# MCU.net
KiCad netlist of a schematic drawn in Altium Designer
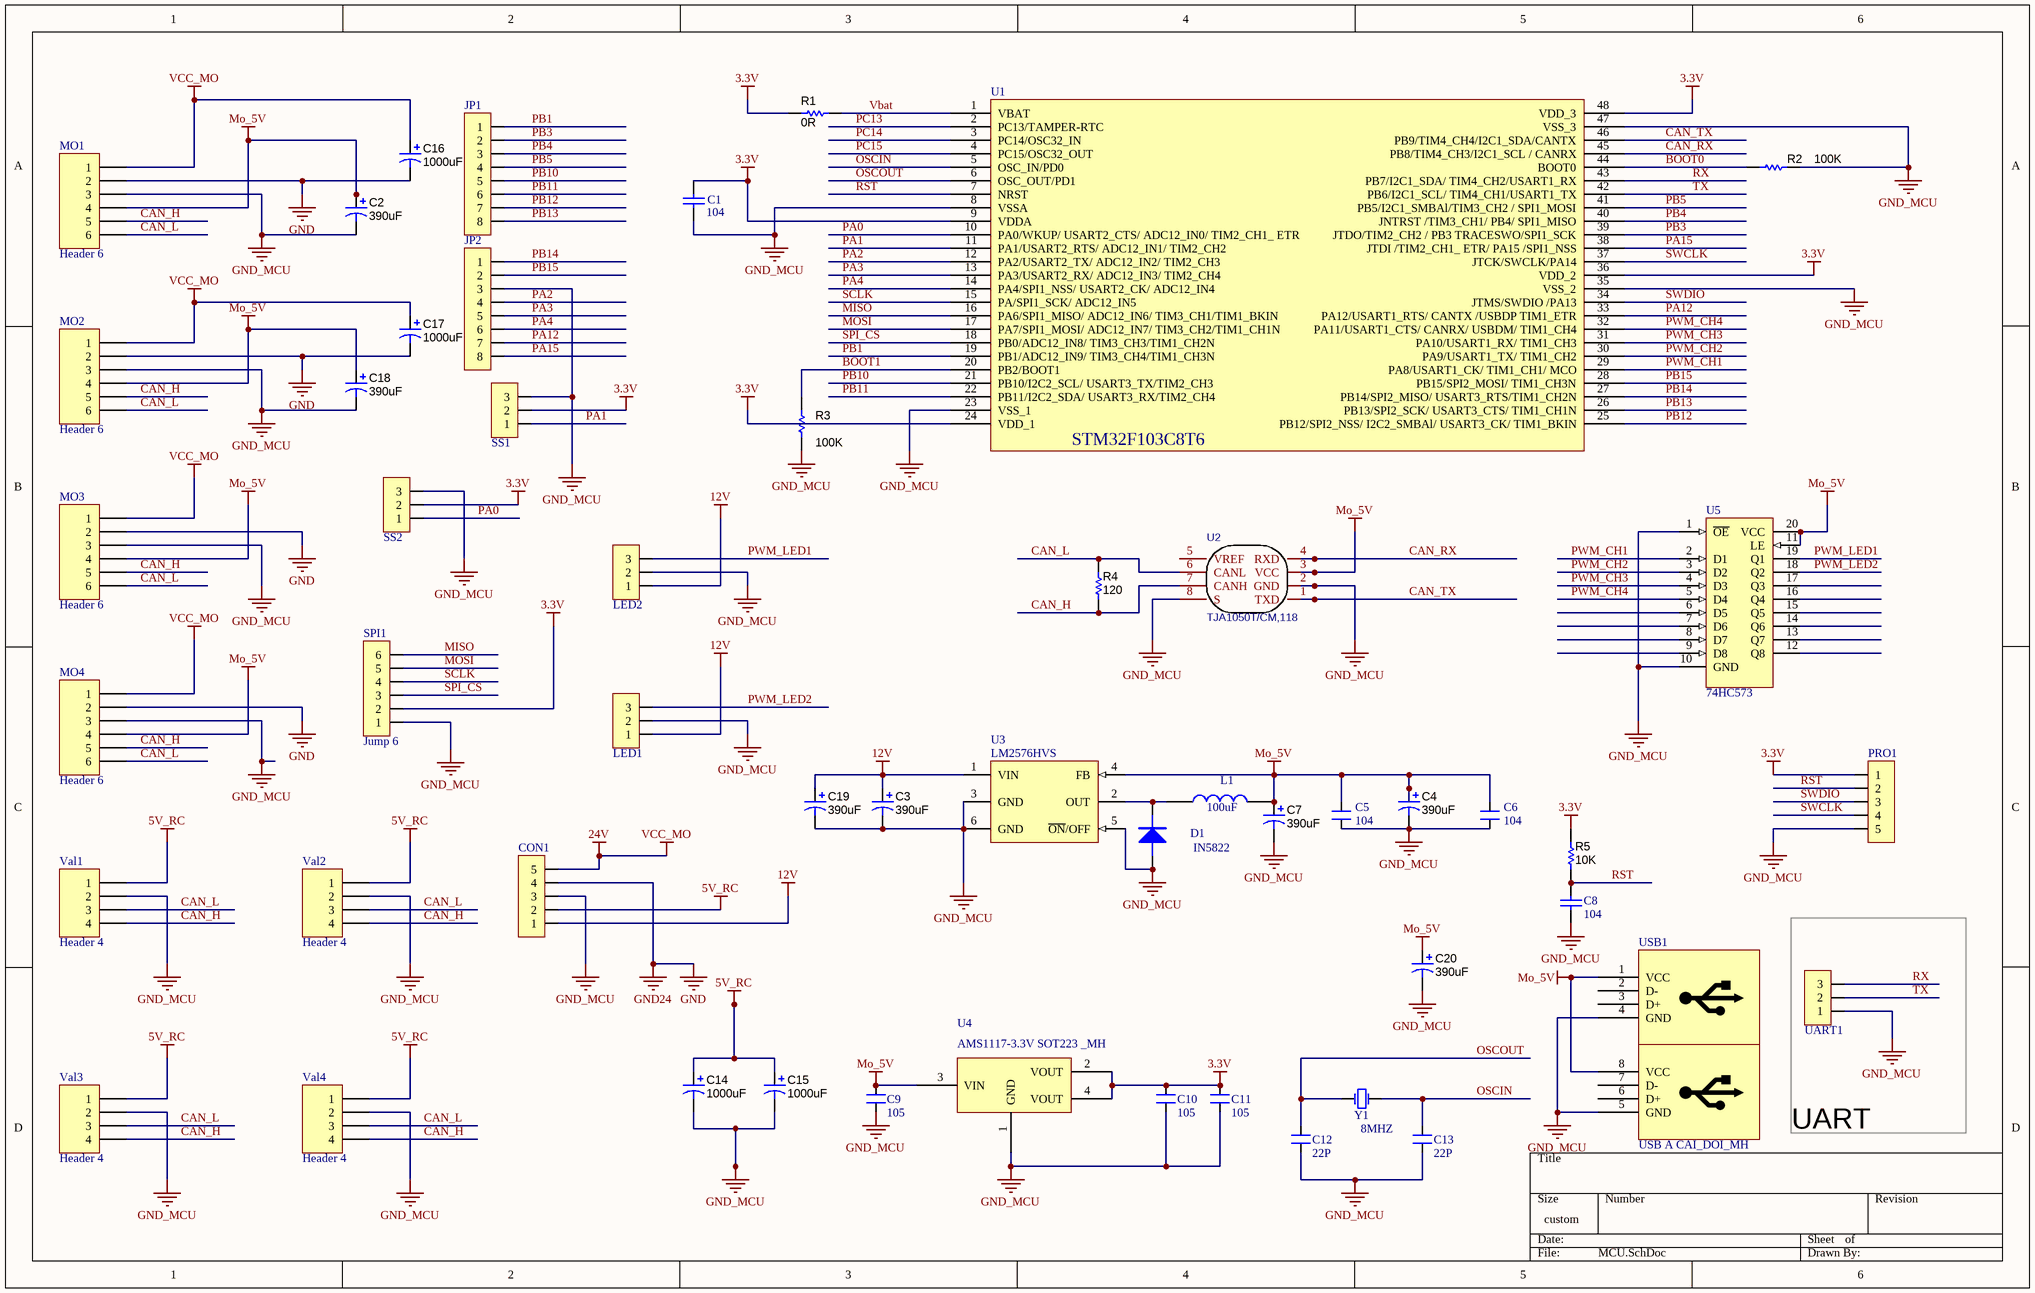
[diagram p0: MCU.SchDoc]

(export (version "E")
  (design (tool "Eeschema 10.0.6"))
  (components
    (comp (ref "C1")
      (value "104")
      (footprint "0805_HV")
      (description "Ceramic Chip Capacitor - Standard")
      (fields (field (name "PUBLISHER") "Altium Limited"))
      (libsource (lib "mySch") (part "Capacitor 0805"))
    )
    (comp (ref "C2")
      (value "390uF")
      (footprint "CP1/3.0")
      (fields
        (field (name "PARTNUMBER") "UHW1H391MPD6")
        (field (name "MANUFACTURER") "Nichicon")
        (field (name "VALUEDISPLAYED") "390uF")
        (field (name "PUBLISHER") "Texas Instruments")
      )
      (libsource (lib "mySch") (part "Capacitor TuHoa"))
    )
    (comp (ref "C3")
      (value "390uF")
      (footprint "CP1/3.0")
      (fields
        (field (name "PARTNUMBER") "UHW1H391MPD6")
        (field (name "MANUFACTURER") "Nichicon")
        (field (name "VALUEDISPLAYED") "390uF")
        (field (name "PUBLISHER") "Texas Instruments")
      )
      (libsource (lib "mySch") (part "Capacitor TuHoa"))
    )
    (comp (ref "C4")
      (value "390uF")
      (footprint "CP1/3.0")
      (fields
        (field (name "PARTNUMBER") "UHW1H391MPD6")
        (field (name "MANUFACTURER") "Nichicon")
        (field (name "VALUEDISPLAYED") "390uF")
        (field (name "PUBLISHER") "Texas Instruments")
      )
      (libsource (lib "mySch") (part "Capacitor TuHoa"))
    )
    (comp (ref "C5")
      (value "104")
      (footprint "0805_HV")
      (description "Cap SMD")
      (libsource (lib "hatcatbietbay") (part "CM"))
    )
    (comp (ref "C6")
      (value "104")
      (footprint "0805_HV")
      (description "Cap SMD")
      (libsource (lib "hatcatbietbay") (part "CM"))
    )
    (comp (ref "C7")
      (value "390uF")
      (footprint "CP1/3.0")
      (fields
        (field (name "PARTNUMBER") "UHW1H391MPD6")
        (field (name "MANUFACTURER") "Nichicon")
        (field (name "VALUEDISPLAYED") "390uF")
        (field (name "PUBLISHER") "Texas Instruments")
      )
      (libsource (lib "mySch") (part "Capacitor TuHoa"))
    )
    (comp (ref "C8")
      (value "104")
      (footprint "0805_HV")
      (description "Ceramic Chip Capacitor - Standard")
      (fields (field (name "PUBLISHER") "Altium Limited"))
      (libsource (lib "mySch") (part "Capacitor 0805"))
    )
    (comp (ref "C9")
      (value "105")
      (footprint "0805_HV")
      (description "Cap SMD")
      (libsource (lib "hatcatbietbay") (part "CM"))
    )
    (comp (ref "C10")
      (value "105")
      (footprint "0805_HV")
      (description "Cap SMD")
      (libsource (lib "hatcatbietbay") (part "CM"))
    )
    (comp (ref "C11")
      (value "105")
      (footprint "0805_HV")
      (description "Cap SMD")
      (libsource (lib "hatcatbietbay") (part "CM"))
    )
    (comp (ref "C12")
      (value "22P")
      (footprint "0805_HV")
      (description "Cap SMD")
      (libsource (lib "hatcatbietbay") (part "CM"))
    )
    (comp (ref "C13")
      (value "22P")
      (footprint "0805_HV")
      (description "Cap SMD")
      (libsource (lib "hatcatbietbay") (part "CM"))
    )
    (comp (ref "C14")
      (value "390uF")
      (footprint "CAP_12.5 X 25")
      (description "CAP ALUM 390UF 20% 50V RADIAL")
      (fields
        (field (name "PARTNUMBER") "UHW1H391MPD6")
        (field (name "MANUFACTURER") "Nichicon")
        (field (name "VALUEDISPLAYED") "1000uF")
        (field (name "PUBLISHER") "Texas Instruments")
      )
      (libsource (lib "mySch") (part "Capacitor TuHoa"))
    )
    (comp (ref "C15")
      (value "390uF")
      (footprint "CAP_12.5 X 25")
      (description "CAP ALUM 390UF 20% 50V RADIAL")
      (fields
        (field (name "PARTNUMBER") "UHW1H391MPD6")
        (field (name "MANUFACTURER") "Nichicon")
        (field (name "VALUEDISPLAYED") "1000uF")
        (field (name "PUBLISHER") "Texas Instruments")
      )
      (libsource (lib "mySch") (part "Capacitor TuHoa"))
    )
    (comp (ref "C16")
      (value "390uF")
      (footprint "CAP_12.5 X 25")
      (description "CAP ALUM 390UF 20% 50V RADIAL")
      (fields
        (field (name "PARTNUMBER") "UHW1H391MPD6")
        (field (name "MANUFACTURER") "Nichicon")
        (field (name "VALUEDISPLAYED") "1000uF")
        (field (name "PUBLISHER") "Texas Instruments")
      )
      (libsource (lib "mySch") (part "Capacitor TuHoa"))
    )
    (comp (ref "C17")
      (value "390uF")
      (footprint "CAP_12.5 X 25")
      (description "CAP ALUM 390UF 20% 50V RADIAL")
      (fields
        (field (name "PARTNUMBER") "UHW1H391MPD6")
        (field (name "MANUFACTURER") "Nichicon")
        (field (name "VALUEDISPLAYED") "1000uF")
        (field (name "PUBLISHER") "Texas Instruments")
      )
      (libsource (lib "mySch") (part "Capacitor TuHoa"))
    )
    (comp (ref "C18")
      (value "390uF")
      (footprint "CP1/3.0")
      (fields
        (field (name "PARTNUMBER") "UHW1H391MPD6")
        (field (name "MANUFACTURER") "Nichicon")
        (field (name "VALUEDISPLAYED") "390uF")
        (field (name "PUBLISHER") "Texas Instruments")
      )
      (libsource (lib "mySch") (part "Capacitor TuHoa"))
    )
    (comp (ref "C19")
      (value "390uF")
      (footprint "CP1/3.0")
      (fields
        (field (name "PARTNUMBER") "UHW1H391MPD6")
        (field (name "MANUFACTURER") "Nichicon")
        (field (name "VALUEDISPLAYED") "390uF")
        (field (name "PUBLISHER") "Texas Instruments")
      )
      (libsource (lib "mySch") (part "Capacitor TuHoa"))
    )
    (comp (ref "C20")
      (value "390uF")
      (footprint "CP1/3.0")
      (fields
        (field (name "PARTNUMBER") "UHW1H391MPD6")
        (field (name "MANUFACTURER") "Nichicon")
        (field (name "VALUEDISPLAYED") "390uF")
        (field (name "PUBLISHER") "Texas Instruments")
      )
      (libsource (lib "mySch") (part "Capacitor TuHoa"))
    )
    (comp (ref "CON1")
      (value "CON 5 EDG 5.08_MH")
      (footprint "Con 5 EDG 5.08")
      (description "CON 5 EDG 5.08 (xanh cong)")
      (libsource (lib "MH_DA_THU_VIEN_16122016") (part "CON 5 EDG 5.08_MH"))
    )
    (comp (ref "D1")
      (value "IN5822")
      (footprint "SOD123")
      (description "Diode S4 SOD123 ( 1N5819 SOD123)")
      (libsource (lib "MH_DA_THU_VIEN_16122016") (part "Diode S4 SOD123 ( 1N5819 SOD123)_MH"))
    )
    (comp (ref "JP1")
      (value "Jump 8_MH")
      (footprint "Jump 8")
      (description "Jump 8P 2.54")
      (libsource (lib "MH_DA_THU_VIEN_16122016") (part "Jump 8_MH"))
    )
    (comp (ref "JP2")
      (value "Jump 8_MH")
      (footprint "Jump 8")
      (description "Jump 8P 2.54")
      (libsource (lib "MH_DA_THU_VIEN_16122016") (part "Jump 8_MH"))
    )
    (comp (ref "L1")
      (value "100uF")
      (footprint "IND_2118-V-RC")
      (description "cuon cam")
      (libsource (lib "MH_DA_THU_VIEN_16122016") (part "Inductor Lm2576_MH"))
    )
    (comp (ref "LED1")
      (value "Header 3_MH")
      (footprint "HEADER 3")
      (description "Header 3P XH2.54 thẳng")
      (libsource (lib "MH_DA_THU_VIEN_16122016") (part "Header 3_MH"))
    )
    (comp (ref "LED2")
      (value "Header 3_MH")
      (footprint "HEADER 3")
      (description "Header 3P XH2.54 thẳng")
      (libsource (lib "MH_DA_THU_VIEN_16122016") (part "Header 3_MH"))
    )
    (comp (ref "MO1")
      (value "Header 6")
      (footprint "HEADER 6")
      (description "Header, 6-Pin")
      (fields (field (name "PUBLISHER") "Altium Limited"))
      (libsource (lib "MH_DA_THU_VIEN_16122016") (part "Header 6"))
    )
    (comp (ref "MO2")
      (value "Header 6")
      (footprint "HEADER 6")
      (description "Header, 6-Pin")
      (fields (field (name "PUBLISHER") "Altium Limited"))
      (libsource (lib "MH_DA_THU_VIEN_16122016") (part "Header 6"))
    )
    (comp (ref "MO3")
      (value "Header 6")
      (footprint "HEADER 6")
      (description "Header, 6-Pin")
      (fields (field (name "PUBLISHER") "Altium Limited"))
      (libsource (lib "MH_DA_THU_VIEN_16122016") (part "Header 6"))
    )
    (comp (ref "MO4")
      (value "Header 6")
      (footprint "HEADER 6")
      (description "Header, 6-Pin")
      (fields (field (name "PUBLISHER") "Altium Limited"))
      (libsource (lib "MH_DA_THU_VIEN_16122016") (part "Header 6"))
    )
    (comp (ref "PRO1")
      (value "Header 5_MH")
      (footprint "HEADER 5")
      (description "Header 5P XH2.54 thẳng")
      (libsource (lib "MH_DA_THU_VIEN_16122016") (part "Header 5_MH"))
    )
    (comp (ref "R1")
      (value "0R")
      (footprint "0805_HV")
      (description "RES, 100, 1%, 0.1 W, 0402")
      (fields
        (field (name "PARTNUMBER") "ERJ-2RKF1000X")
        (field (name "MANUFACTURER") "Panasonic")
        (field (name "PUBLISHER") "Texas Instruments")
      )
      (libsource (lib "mySch") (part "R nho"))
    )
    (comp (ref "R2")
      (value "100K")
      (footprint "0805_HV")
      (description "RES, 100, 1%, 0.1 W, 0402")
      (fields
        (field (name "PARTNUMBER") "ERJ-2RKF1000X")
        (field (name "MANUFACTURER") "Panasonic")
        (field (name "PUBLISHER") "Texas Instruments")
      )
      (libsource (lib "mySch") (part "R nho"))
    )
    (comp (ref "R3")
      (value "100K")
      (footprint "0805_HV")
      (description "RES, 100, 1%, 0.1 W, 0402")
      (fields
        (field (name "PARTNUMBER") "ERJ-2RKF1000X")
        (field (name "MANUFACTURER") "Panasonic")
        (field (name "PUBLISHER") "Texas Instruments")
      )
      (libsource (lib "mySch") (part "R nho"))
    )
    (comp (ref "R4")
      (value "120")
      (footprint "0805_HV")
      (description "RES, 100, 1%, 0.1 W, 0402")
      (fields
        (field (name "PARTNUMBER") "ERJ-2RKF1000X")
        (field (name "MANUFACTURER") "Panasonic")
        (field (name "PUBLISHER") "Texas Instruments")
      )
      (libsource (lib "mySch") (part "R nho"))
    )
    (comp (ref "R5")
      (value "10K")
      (footprint "0805_HV")
      (description "RES, 100, 1%, 0.1 W, 0402")
      (fields
        (field (name "PARTNUMBER") "ERJ-2RKF1000X")
        (field (name "MANUFACTURER") "Panasonic")
        (field (name "PUBLISHER") "Texas Instruments")
      )
      (libsource (lib "mySch") (part "R nho"))
    )
    (comp (ref "SPI1")
      (value "Jump 6")
      (footprint "ZH 1.5 6P")
      (description "Jump 6P 2.54")
      (libsource (lib "mySch") (part "Jump 6"))
    )
    (comp (ref "SS1")
      (value "Header 3_MH")
      (footprint "HEADER 3")
      (description "Header 3P XH2.54 thẳng")
      (libsource (lib "MH_DA_THU_VIEN_16122016") (part "Header 3_MH"))
    )
    (comp (ref "SS2")
      (value "Header 3_MH")
      (footprint "HEADER 3")
      (description "Header 3P XH2.54 thẳng")
      (libsource (lib "MH_DA_THU_VIEN_16122016") (part "Header 3_MH"))
    )
    (comp (ref "U1")
      (value "STM32F103C8T6 LQFP48 _MH")
      (footprint "LQFP48")
      (libsource (lib "MH_DA_THU_VIEN_16122016") (part "STM32F103C8T6 LQFP48 _MH"))
    )
    (comp (ref "U2")
      (value "TJA1050T/CM,118")
      (footprint "SOP 8")
      (fields (field (name "BOM_SUPPLIER PART") "C6952"))
      (libsource (lib "Schlib1") (part "TJA1050T/CM,118"))
    )
    (comp (ref "U3")
      (value "LM2576HVS")
      (footprint "TO263-5")
      (description "LM2576HVS-5.0V BUCK 5V 3A TO263-5 _MH")
      (fields
        (field (name "PARTNUMBER") "LM2576T-5.0")
        (field (name "MANUFACTURER") "National Semiconductor")
        (field (name "PUBLISHER") "Altium Limited")
      )
      (libsource (lib "MH_DA_THU_VIEN_16122016") (part "LM2576HVS-5.0V BUCK 5V 3A TO263-5 _MH"))
    )
    (comp (ref "U4")
      (value "AMS1117-3.3V SOT223 _MH")
      (footprint "SOT223")
      (libsource (lib "MH_DA_THU_VIEN_16122016") (part "AMS1117-3.3V SOT223 _MH"))
    )
    (comp (ref "U5")
      (value "74HC573")
      (footprint "SOIC-20")
      (description "Octal D-Type Latch with 3-State Output Non-Inverting")
      (fields (field (name "COPYRIGHT BY") "VanDungEvn@Gmail.com"))
      (libsource (lib "MH_DA_THU_VIEN_16122016") (part "74HC573 DIP20 IC Flip-Flop_MH"))
    )
    (comp (ref "UART1")
      (value "Header 3_MH")
      (footprint "HEADER 3")
      (description "Header 3P XH2.54 thẳng")
      (libsource (lib "MH_DA_THU_VIEN_16122016") (part "Header 3_MH"))
    )
    (comp (ref "USB1")
      (value "USB A CAI_DOI_MH")
      (footprint "USB_KEP")
      (libsource (lib "MH_DA_THU_VIEN_16122016") (part "USB A CAI_DOI_MH"))
    )
    (comp (ref "Val1")
      (value "Header 4")
      (footprint "JST-PH2.00-4P")
      (description "Header, 4-Pin")
      (fields (field (name "PUBLISHER") "Altium Limited"))
      (libsource (lib "Miscellaneous Connectors") (part "Header 4"))
    )
    (comp (ref "Val2")
      (value "Header 4")
      (footprint "JST-PH2.00-4P")
      (description "Header, 4-Pin")
      (fields (field (name "PUBLISHER") "Altium Limited"))
      (libsource (lib "Miscellaneous Connectors") (part "Header 4"))
    )
    (comp (ref "Val3")
      (value "Header 4")
      (footprint "JST-PH2.00-4P")
      (description "Header, 4-Pin")
      (fields (field (name "PUBLISHER") "Altium Limited"))
      (libsource (lib "Miscellaneous Connectors") (part "Header 4"))
    )
    (comp (ref "Val4")
      (value "Header 4")
      (footprint "JST-PH2.00-4P")
      (description "Header, 4-Pin")
      (fields (field (name "PUBLISHER") "Altium Limited"))
      (libsource (lib "Miscellaneous Connectors") (part "Header 4"))
    )
    (comp (ref "Y1")
      (value "8MHZ")
      (footprint "XT2")
      (description "Crystal Oscillator")
      (fields (field (name "PUBLISHER") "Altium Limited"))
      (libsource (lib "MH_DA_THU_VIEN_16122016") (part "CRYSTAL_49S DIP_MH"))
    )
  )
  (nets
    (net (code "1") (name "/BOOT0") (class "Default")
      (node (ref "R2") (pin "2") (pinfunction "2_2") (pintype "passive"))
      (node (ref "U1") (pin "44") (pinfunction "BOOT0_44") (pintype "passive"))
    )
    (net (code "2") (name "/BOOT1") (class "Default")
      (node (ref "R3") (pin "1") (pinfunction "1_1") (pintype "passive"))
      (node (ref "U1") (pin "20") (pinfunction "PB2/BOOT1_20") (pintype "passive"))
    )
    (net (code "3") (name "/CAN_H") (class "Default")
      (node (ref "MO1") (pin "5") (pinfunction "5_5") (pintype "passive"))
      (node (ref "MO2") (pin "5") (pinfunction "5_5") (pintype "passive"))
      (node (ref "MO3") (pin "5") (pinfunction "5_5") (pintype "passive"))
      (node (ref "MO4") (pin "5") (pinfunction "5_5") (pintype "passive"))
      (node (ref "R4") (pin "2") (pinfunction "2_2") (pintype "passive"))
      (node (ref "U2") (pin "7") (pinfunction "CANH_7") (pintype "passive"))
      (node (ref "Val1") (pin "4") (pinfunction "4_4") (pintype "passive"))
      (node (ref "Val2") (pin "4") (pinfunction "4_4") (pintype "passive"))
      (node (ref "Val3") (pin "4") (pinfunction "4_4") (pintype "passive"))
      (node (ref "Val4") (pin "4") (pinfunction "4_4") (pintype "passive"))
    )
    (net (code "4") (name "/CAN_L") (class "Default")
      (node (ref "MO1") (pin "6") (pinfunction "6_6") (pintype "passive"))
      (node (ref "MO2") (pin "6") (pinfunction "6_6") (pintype "passive"))
      (node (ref "MO3") (pin "6") (pinfunction "6_6") (pintype "passive"))
      (node (ref "MO4") (pin "6") (pinfunction "6_6") (pintype "passive"))
      (node (ref "R4") (pin "1") (pinfunction "1_1") (pintype "passive"))
      (node (ref "U2") (pin "6") (pinfunction "CANL_6") (pintype "passive"))
      (node (ref "Val1") (pin "3") (pinfunction "3_3") (pintype "passive"))
      (node (ref "Val2") (pin "3") (pinfunction "3_3") (pintype "passive"))
      (node (ref "Val3") (pin "3") (pinfunction "3_3") (pintype "passive"))
      (node (ref "Val4") (pin "3") (pinfunction "3_3") (pintype "passive"))
    )
    (net (code "5") (name "/CAN_RX") (class "Default")
      (node (ref "U1") (pin "45") (pinfunction "PB8/TIM4_CH3/I2C1_SCL_/_CANRX_45") (pintype "passive"))
      (node (ref "U2") (pin "4") (pinfunction "RXD_4") (pintype "passive"))
    )
    (net (code "6") (name "/CAN_TX") (class "Default")
      (node (ref "U1") (pin "46") (pinfunction "PB9/TIM4_CH4/I2C1_SDA/CANTX_46") (pintype "passive"))
      (node (ref "U2") (pin "1") (pinfunction "TXD_1") (pintype "passive"))
    )
    (net (code "7") (name "/MISO") (class "Default")
      (node (ref "SPI1") (pin "6") (pinfunction "6_6") (pintype "passive"))
      (node (ref "U1") (pin "16") (pinfunction "PA6/SPI1_MISO/_ADC12_IN6/_TIM3_CH1/TIM1_BKIN_16") (pintype "passive"))
    )
    (net (code "8") (name "/MOSI") (class "Default")
      (node (ref "SPI1") (pin "5") (pinfunction "5_5") (pintype "passive"))
      (node (ref "U1") (pin "17") (pinfunction "PA7/SPI1_MOSI/_ADC12_IN7/_TIM3_CH2/TIM1_CH1N_17") (pintype "passive"))
    )
    (net (code "9") (name "/OSCIN") (class "Default")
      (node (ref "C13") (pin "2") (pinfunction "2_2") (pintype "passive"))
      (node (ref "U1") (pin "5") (pinfunction "OSC_IN/PD0_5") (pintype "passive"))
      (node (ref "Y1") (pin "2") (pinfunction "OSC2_2") (pintype "passive"))
    )
    (net (code "10") (name "/OSCOUT") (class "Default")
      (node (ref "C12") (pin "2") (pinfunction "2_2") (pintype "passive"))
      (node (ref "U1") (pin "6") (pinfunction "OSC_OUT/PD1_6") (pintype "passive"))
      (node (ref "Y1") (pin "1") (pinfunction "OSC1_1") (pintype "passive"))
    )
    (net (code "11") (name "/PA0") (class "Default")
      (node (ref "SS2") (pin "1") (pinfunction "1_1") (pintype "passive"))
      (node (ref "U1") (pin "10") (pinfunction "PA0/WKUP/_USART2_CTS/_ADC12_IN0/_TIM2_CH1__ETR_10") (pintype "passive"))
    )
    (net (code "12") (name "/PA1") (class "Default")
      (node (ref "SS1") (pin "1") (pinfunction "1_1") (pintype "passive"))
      (node (ref "U1") (pin "11") (pinfunction "PA1/USART2_RTS/_ADC12_IN1/_TIM2_CH2_11") (pintype "passive"))
    )
    (net (code "13") (name "/PA2") (class "Default")
      (node (ref "JP2") (pin "4") (pinfunction "4_4") (pintype "passive"))
      (node (ref "U1") (pin "12") (pinfunction "PA2/USART2_TX/_ADC12_IN2/_TIM2_CH3_12") (pintype "passive"))
    )
    (net (code "14") (name "/PA3") (class "Default")
      (node (ref "JP2") (pin "5") (pinfunction "5_5") (pintype "passive"))
      (node (ref "U1") (pin "13") (pinfunction "PA3/USART2_RX/_ADC12_IN3/_TIM2_CH4_13") (pintype "passive"))
    )
    (net (code "15") (name "/PA4") (class "Default")
      (node (ref "JP2") (pin "6") (pinfunction "6_6") (pintype "passive"))
      (node (ref "U1") (pin "14") (pinfunction "PA4/SPI1_NSS/_USART2_CK/_ADC12_IN4_14") (pintype "passive"))
    )
    (net (code "16") (name "/PA12") (class "Default")
      (node (ref "JP2") (pin "7") (pinfunction "7_7") (pintype "passive"))
      (node (ref "U1") (pin "33") (pinfunction "PA12/USART1_RTS/_CANTX_/USBDP_TIM1_ETR_33") (pintype "passive"))
    )
    (net (code "17") (name "/PA15") (class "Default")
      (node (ref "JP2") (pin "8") (pinfunction "8_8") (pintype "passive"))
      (node (ref "U1") (pin "38") (pinfunction "JTDI_/TIM2_CH1__ETR/_PA15_/SPI1_NSS_38") (pintype "passive"))
    )
    (net (code "18") (name "/PB1") (class "Default")
      (node (ref "JP1") (pin "1") (pinfunction "1_1") (pintype "passive"))
      (node (ref "U1") (pin "19") (pinfunction "PB1/ADC12_IN9/_TIM3_CH4/TIM1_CH3N_19") (pintype "passive"))
    )
    (net (code "19") (name "/PB3") (class "Default")
      (node (ref "JP1") (pin "2") (pinfunction "2_2") (pintype "passive"))
      (node (ref "U1") (pin "39") (pinfunction "JTDO/TIM2_CH2_/_PB3_TRACESWO/SPI1_SCK_39") (pintype "passive"))
    )
    (net (code "20") (name "/PB4") (class "Default")
      (node (ref "JP1") (pin "3") (pinfunction "3_3") (pintype "passive"))
      (node (ref "U1") (pin "40") (pinfunction "JNTRST_/TIM3_CH1/_PB4/_SPI1_MISO_40") (pintype "passive"))
    )
    (net (code "21") (name "/PB5") (class "Default")
      (node (ref "JP1") (pin "4") (pinfunction "4_4") (pintype "passive"))
      (node (ref "U1") (pin "41") (pinfunction "PB5/I2C1_SMBAl/TIM3_CH2_/_SPI1_MOSI_41") (pintype "passive"))
    )
    (net (code "22") (name "/PB10") (class "Default")
      (node (ref "JP1") (pin "5") (pinfunction "5_5") (pintype "passive"))
      (node (ref "U1") (pin "21") (pinfunction "PB10/I2C2_SCL/_USART3_TX/TIM2_CH3_21") (pintype "passive"))
    )
    (net (code "23") (name "/PB11") (class "Default")
      (node (ref "JP1") (pin "6") (pinfunction "6_6") (pintype "passive"))
      (node (ref "U1") (pin "22") (pinfunction "PB11/I2C2_SDA/_USART3_RX/TIM2_CH4_22") (pintype "passive"))
    )
    (net (code "24") (name "/PB12") (class "Default")
      (node (ref "JP1") (pin "7") (pinfunction "7_7") (pintype "passive"))
      (node (ref "U1") (pin "25") (pinfunction "PB12/SPI2_NSS/_I2C2_SMBAl/_USART3_CK/_TIM1_BKIN_25") (pintype "passive"))
    )
    (net (code "25") (name "/PB13") (class "Default")
      (node (ref "JP1") (pin "8") (pinfunction "8_8") (pintype "passive"))
      (node (ref "U1") (pin "26") (pinfunction "PB13/SPI2_SCK/_USART3_CTS/_TIM1_CH1N_26") (pintype "passive"))
    )
    (net (code "26") (name "/PB14") (class "Default")
      (node (ref "JP2") (pin "1") (pinfunction "1_1") (pintype "passive"))
      (node (ref "U1") (pin "27") (pinfunction "PB14/SPI2_MISO/_USART3_RTS/TIM1_CH2N_27") (pintype "passive"))
    )
    (net (code "27") (name "/PB15") (class "Default")
      (node (ref "JP2") (pin "2") (pinfunction "2_2") (pintype "passive"))
      (node (ref "U1") (pin "28") (pinfunction "PB15/SPI2_MOSI/_TIM1_CH3N_28") (pintype "passive"))
    )
    (net (code "28") (name "/PC13") (class "Default")
      (node (ref "U1") (pin "2") (pinfunction "PC13/TAMPER-RTC_2") (pintype "passive"))
    )
    (net (code "29") (name "/PC14") (class "Default")
      (node (ref "U1") (pin "3") (pinfunction "PC14/OSC32_IN_3") (pintype "passive"))
    )
    (net (code "30") (name "/PC15") (class "Default")
      (node (ref "U1") (pin "4") (pinfunction "PC15/OSC32_OUT_4") (pintype "passive"))
    )
    (net (code "31") (name "/PWM_CH1") (class "Default")
      (node (ref "U1") (pin "29") (pinfunction "PA8/USART1_CK/_TIM1_CH1/_MCO_29") (pintype "passive"))
      (node (ref "U5") (pin "2") (pinfunction "D1_2") (pintype "input"))
    )
    (net (code "32") (name "/PWM_CH2") (class "Default")
      (node (ref "U1") (pin "30") (pinfunction "PA9/USART1_TX/_TIM1_CH2_30") (pintype "passive"))
      (node (ref "U5") (pin "3") (pinfunction "D2_3") (pintype "input"))
    )
    (net (code "33") (name "/PWM_CH3") (class "Default")
      (node (ref "U1") (pin "31") (pinfunction "PA10/USART1_RX/_TIM1_CH3_31") (pintype "passive"))
      (node (ref "U5") (pin "4") (pinfunction "D3_4") (pintype "input"))
    )
    (net (code "34") (name "/PWM_CH4") (class "Default")
      (node (ref "U1") (pin "32") (pinfunction "PA11/USART1_CTS/_CANRX/_USBDM/_TIM1_CH4_32") (pintype "passive"))
      (node (ref "U5") (pin "5") (pinfunction "D4_5") (pintype "input"))
    )
    (net (code "35") (name "/PWM_LED1") (class "Default")
      (node (ref "LED2") (pin "3") (pinfunction "3_3") (pintype "passive"))
      (node (ref "U5") (pin "19") (pinfunction "Q1_19") (pintype "tri_state"))
    )
    (net (code "36") (name "/PWM_LED2") (class "Default")
      (node (ref "LED1") (pin "3") (pinfunction "3_3") (pintype "passive"))
      (node (ref "U5") (pin "18") (pinfunction "Q2_18") (pintype "tri_state"))
    )
    (net (code "37") (name "/RST") (class "Default")
      (node (ref "C8") (pin "2") (pinfunction "2_2") (pintype "passive"))
      (node (ref "PRO1") (pin "2") (pinfunction "2_2") (pintype "passive"))
      (node (ref "R5") (pin "1") (pinfunction "1_1") (pintype "passive"))
      (node (ref "U1") (pin "7") (pinfunction "NRST_7") (pintype "passive"))
    )
    (net (code "38") (name "/RX") (class "Default")
      (node (ref "U1") (pin "43") (pinfunction "PB7/I2C1_SDA/_TIM4_CH2/USART1_RX_43") (pintype "passive"))
      (node (ref "UART1") (pin "3") (pinfunction "3_3") (pintype "passive"))
    )
    (net (code "39") (name "/SCLK") (class "Default")
      (node (ref "SPI1") (pin "4") (pinfunction "4_4") (pintype "passive"))
      (node (ref "U1") (pin "15") (pinfunction "PA/SPI1_SCK/_ADC12_IN5_15") (pintype "passive"))
    )
    (net (code "40") (name "/SPI_CS") (class "Default")
      (node (ref "SPI1") (pin "3") (pinfunction "3_3") (pintype "passive"))
      (node (ref "U1") (pin "18") (pinfunction "PB0/ADC12_IN8/_TIM3_CH3/TIM1_CH2N_18") (pintype "passive"))
    )
    (net (code "41") (name "/SWCLK") (class "Default")
      (node (ref "PRO1") (pin "4") (pinfunction "4_4") (pintype "passive"))
      (node (ref "U1") (pin "37") (pinfunction "JTCK/SWCLK/PA14_37") (pintype "passive"))
    )
    (net (code "42") (name "/SWDIO") (class "Default")
      (node (ref "PRO1") (pin "3") (pinfunction "3_3") (pintype "passive"))
      (node (ref "U1") (pin "34") (pinfunction "JTMS/SWDIO_/PA13_34") (pintype "passive"))
    )
    (net (code "43") (name "/TX") (class "Default")
      (node (ref "U1") (pin "42") (pinfunction "PB6/I2C1_SCL/_TIM4_CH1/USART1_TX_42") (pintype "passive"))
      (node (ref "UART1") (pin "2") (pinfunction "2_2") (pintype "passive"))
    )
    (net (code "44") (name "/Vbat") (class "Default")
      (node (ref "R1") (pin "1") (pinfunction "1_1") (pintype "passive"))
      (node (ref "U1") (pin "1") (pinfunction "VBAT_1") (pintype "passive"))
    )
    (net (code "45") (name "3.3V") (class "Default")
      (node (ref "C1") (pin "2") (pinfunction "2_2") (pintype "passive"))
      (node (ref "C10") (pin "2") (pinfunction "2_2") (pintype "passive"))
      (node (ref "C11") (pin "2") (pinfunction "2_2") (pintype "passive"))
      (node (ref "PRO1") (pin "1") (pinfunction "1_1") (pintype "passive"))
      (node (ref "R1") (pin "2") (pinfunction "2_2") (pintype "passive"))
      (node (ref "R5") (pin "2") (pinfunction "2_2") (pintype "passive"))
      (node (ref "SPI1") (pin "2") (pinfunction "2_2") (pintype "passive"))
      (node (ref "SS1") (pin "2") (pinfunction "2_2") (pintype "passive"))
      (node (ref "SS2") (pin "2") (pinfunction "2_2") (pintype "passive"))
      (node (ref "U1") (pin "24") (pinfunction "VDD_1_24") (pintype "passive"))
      (node (ref "U1") (pin "36") (pinfunction "VDD_2_36") (pintype "passive"))
      (node (ref "U1") (pin "48") (pinfunction "VDD_3_48") (pintype "passive"))
      (node (ref "U1") (pin "9") (pinfunction "VDDA_9") (pintype "passive"))
      (node (ref "U4") (pin "2") (pinfunction "VOUT_2") (pintype "passive"))
      (node (ref "U4") (pin "4") (pinfunction "VOUT_4") (pintype "passive"))
    )
    (net (code "46") (name "5V_RC") (class "Default")
      (node (ref "C14") (pin "1") (pinfunction "+_1") (pintype "passive"))
      (node (ref "C15") (pin "1") (pinfunction "+_1") (pintype "passive"))
      (node (ref "CON1") (pin "2") (pinfunction "2_2") (pintype "passive"))
      (node (ref "Val1") (pin "1") (pinfunction "1_1") (pintype "passive"))
      (node (ref "Val2") (pin "1") (pinfunction "1_1") (pintype "passive"))
      (node (ref "Val3") (pin "1") (pinfunction "1_1") (pintype "passive"))
      (node (ref "Val4") (pin "1") (pinfunction "1_1") (pintype "passive"))
    )
    (net (code "47") (name "12V") (class "Default")
      (node (ref "C19") (pin "1") (pinfunction "+_1") (pintype "passive"))
      (node (ref "C3") (pin "1") (pinfunction "+_1") (pintype "passive"))
      (node (ref "CON1") (pin "1") (pinfunction "1_1") (pintype "passive"))
      (node (ref "LED1") (pin "1") (pinfunction "1_1") (pintype "passive"))
      (node (ref "LED2") (pin "1") (pinfunction "1_1") (pintype "passive"))
      (node (ref "U3") (pin "1") (pinfunction "VIN_1") (pintype "power_in"))
    )
    (net (code "48") (name "24V") (class "Default")
      (node (ref "C16") (pin "1") (pinfunction "+_1") (pintype "passive"))
      (node (ref "C17") (pin "1") (pinfunction "+_1") (pintype "passive"))
      (node (ref "CON1") (pin "5") (pinfunction "5_5") (pintype "passive"))
      (node (ref "MO1") (pin "1") (pinfunction "1_1") (pintype "passive"))
      (node (ref "MO2") (pin "1") (pinfunction "1_1") (pintype "passive"))
      (node (ref "MO3") (pin "1") (pinfunction "1_1") (pintype "passive"))
      (node (ref "MO4") (pin "1") (pinfunction "1_1") (pintype "passive"))
    )
    (net (code "49") (name "GND") (class "Default")
      (node (ref "C16") (pin "2") (pinfunction "-_2") (pintype "passive"))
      (node (ref "C17") (pin "2") (pinfunction "-_2") (pintype "passive"))
      (node (ref "CON1") (pin "4") (pinfunction "4_4") (pintype "passive"))
      (node (ref "MO1") (pin "2") (pinfunction "2_2") (pintype "passive"))
      (node (ref "MO2") (pin "2") (pinfunction "2_2") (pintype "passive"))
      (node (ref "MO3") (pin "2") (pinfunction "2_2") (pintype "passive"))
      (node (ref "MO4") (pin "2") (pinfunction "2_2") (pintype "passive"))
    )
    (net (code "50") (name "GND_MCU") (class "Default")
      (node (ref "C1") (pin "1") (pinfunction "1_1") (pintype "passive"))
      (node (ref "C10") (pin "1") (pinfunction "1_1") (pintype "passive"))
      (node (ref "C11") (pin "1") (pinfunction "1_1") (pintype "passive"))
      (node (ref "C12") (pin "1") (pinfunction "1_1") (pintype "passive"))
      (node (ref "C13") (pin "1") (pinfunction "1_1") (pintype "passive"))
      (node (ref "C14") (pin "2") (pinfunction "-_2") (pintype "passive"))
      (node (ref "C15") (pin "2") (pinfunction "-_2") (pintype "passive"))
      (node (ref "C18") (pin "2") (pinfunction "-_2") (pintype "passive"))
      (node (ref "C19") (pin "2") (pinfunction "-_2") (pintype "passive"))
      (node (ref "C2") (pin "2") (pinfunction "-_2") (pintype "passive"))
      (node (ref "C20") (pin "2") (pinfunction "-_2") (pintype "passive"))
      (node (ref "C3") (pin "2") (pinfunction "-_2") (pintype "passive"))
      (node (ref "C4") (pin "2") (pinfunction "-_2") (pintype "passive"))
      (node (ref "C5") (pin "1") (pinfunction "1_1") (pintype "passive"))
      (node (ref "C6") (pin "1") (pinfunction "1_1") (pintype "passive"))
      (node (ref "C7") (pin "2") (pinfunction "-_2") (pintype "passive"))
      (node (ref "C8") (pin "1") (pinfunction "1_1") (pintype "passive"))
      (node (ref "C9") (pin "1") (pinfunction "1_1") (pintype "passive"))
      (node (ref "CON1") (pin "3") (pinfunction "3_3") (pintype "passive"))
      (node (ref "D1") (pin "1") (pinfunction "1_1") (pintype "passive"))
      (node (ref "JP2") (pin "3") (pinfunction "3_3") (pintype "passive"))
      (node (ref "LED1") (pin "2") (pinfunction "2_2") (pintype "passive"))
      (node (ref "LED2") (pin "2") (pinfunction "2_2") (pintype "passive"))
      (node (ref "MO1") (pin "3") (pinfunction "3_3") (pintype "passive"))
      (node (ref "MO2") (pin "3") (pinfunction "3_3") (pintype "passive"))
      (node (ref "MO3") (pin "3") (pinfunction "3_3") (pintype "passive"))
      (node (ref "MO4") (pin "3") (pinfunction "3_3") (pintype "passive"))
      (node (ref "PRO1") (pin "5") (pinfunction "5_5") (pintype "passive"))
      (node (ref "R2") (pin "1") (pinfunction "1_1") (pintype "passive"))
      (node (ref "R3") (pin "2") (pinfunction "2_2") (pintype "passive"))
      (node (ref "SPI1") (pin "1") (pinfunction "1_1") (pintype "passive"))
      (node (ref "SS1") (pin "3") (pinfunction "3_3") (pintype "passive"))
      (node (ref "SS2") (pin "3") (pinfunction "3_3") (pintype "passive"))
      (node (ref "U1") (pin "23") (pinfunction "VSS_1_23") (pintype "passive"))
      (node (ref "U1") (pin "35") (pinfunction "VSS_2_35") (pintype "passive"))
      (node (ref "U1") (pin "47") (pinfunction "VSS_3_47") (pintype "passive"))
      (node (ref "U1") (pin "8") (pinfunction "VSSA_8") (pintype "passive"))
      (node (ref "U2") (pin "2") (pinfunction "GND_2") (pintype "passive"))
      (node (ref "U2") (pin "8") (pinfunction "S_8") (pintype "passive"))
      (node (ref "U3") (pin "3") (pinfunction "GND_3") (pintype "power_in"))
      (node (ref "U3") (pin "5") (pinfunction "~{ON}/OFF_5") (pintype "input"))
      (node (ref "U3") (pin "6") (pinfunction "GND_6") (pintype "passive"))
      (node (ref "U4") (pin "1") (pinfunction "GND_1") (pintype "passive"))
      (node (ref "U5") (pin "1") (pinfunction "~{OE}_1") (pintype "input"))
      (node (ref "U5") (pin "10") (pinfunction "GND_10") (pintype "tri_state"))
      (node (ref "UART1") (pin "1") (pinfunction "1_1") (pintype "passive"))
      (node (ref "USB1") (pin "4") (pinfunction "GND_4") (pintype "passive"))
      (node (ref "USB1") (pin "5") (pinfunction "GND_5") (pintype "passive"))
      (node (ref "Val1") (pin "2") (pinfunction "2_2") (pintype "passive"))
      (node (ref "Val2") (pin "2") (pinfunction "2_2") (pintype "passive"))
      (node (ref "Val3") (pin "2") (pinfunction "2_2") (pintype "passive"))
      (node (ref "Val4") (pin "2") (pinfunction "2_2") (pintype "passive"))
    )
    (net (code "51") (name "Mo_5V") (class "Default")
      (node (ref "C18") (pin "1") (pinfunction "+_1") (pintype "passive"))
      (node (ref "C2") (pin "1") (pinfunction "+_1") (pintype "passive"))
      (node (ref "C20") (pin "1") (pinfunction "+_1") (pintype "passive"))
      (node (ref "C4") (pin "1") (pinfunction "+_1") (pintype "passive"))
      (node (ref "C5") (pin "2") (pinfunction "2_2") (pintype "passive"))
      (node (ref "C6") (pin "2") (pinfunction "2_2") (pintype "passive"))
      (node (ref "C7") (pin "1") (pinfunction "+_1") (pintype "passive"))
      (node (ref "C9") (pin "2") (pinfunction "2_2") (pintype "passive"))
      (node (ref "L1") (pin "2") (pinfunction "2_2") (pintype "passive"))
      (node (ref "MO1") (pin "4") (pinfunction "4_4") (pintype "passive"))
      (node (ref "MO2") (pin "4") (pinfunction "4_4") (pintype "passive"))
      (node (ref "MO3") (pin "4") (pinfunction "4_4") (pintype "passive"))
      (node (ref "MO4") (pin "4") (pinfunction "4_4") (pintype "passive"))
      (node (ref "U2") (pin "3") (pinfunction "VCC_3") (pintype "passive"))
      (node (ref "U3") (pin "4") (pinfunction "FB_4") (pintype "input"))
      (node (ref "U4") (pin "3") (pinfunction "VIN_3") (pintype "passive"))
      (node (ref "U5") (pin "11") (pinfunction "LE_11") (pintype "input"))
      (node (ref "U5") (pin "20") (pinfunction "VCC_20") (pintype "tri_state"))
      (node (ref "USB1") (pin "1") (pinfunction "VCC_1") (pintype "passive"))
      (node (ref "USB1") (pin "8") (pinfunction "VCC_8") (pintype "passive"))
    )
    (net (code "52") (name "Net-(U3-OUT)") (class "Default")
      (node (ref "D1") (pin "2") (pinfunction "2_2") (pintype "passive"))
      (node (ref "L1") (pin "1") (pinfunction "1_1") (pintype "passive"))
      (node (ref "U3") (pin "2") (pinfunction "OUT_2") (pintype "power_in"))
    )
    (net (code "53") (name "unconnected-(U2-VREF-Pad5)") (class "Default")
      (node (ref "U2") (pin "5") (pinfunction "VREF_5") (pintype "passive"))
    )
    (net (code "54") (name "unconnected-(U5-D5-Pad6)") (class "Default")
      (node (ref "U5") (pin "6") (pinfunction "D5_6") (pintype "input"))
    )
    (net (code "55") (name "unconnected-(U5-D6-Pad7)") (class "Default")
      (node (ref "U5") (pin "7") (pinfunction "D6_7") (pintype "input"))
    )
    (net (code "56") (name "unconnected-(U5-D7-Pad8)") (class "Default")
      (node (ref "U5") (pin "8") (pinfunction "D7_8") (pintype "input"))
    )
    (net (code "57") (name "unconnected-(U5-D8-Pad9)") (class "Default")
      (node (ref "U5") (pin "9") (pinfunction "D8_9") (pintype "input"))
    )
    (net (code "58") (name "unconnected-(U5-Q3-Pad17)") (class "Default")
      (node (ref "U5") (pin "17") (pinfunction "Q3_17") (pintype "tri_state"))
    )
    (net (code "59") (name "unconnected-(U5-Q4-Pad16)") (class "Default")
      (node (ref "U5") (pin "16") (pinfunction "Q4_16") (pintype "tri_state"))
    )
    (net (code "60") (name "unconnected-(U5-Q5-Pad15)") (class "Default")
      (node (ref "U5") (pin "15") (pinfunction "Q5_15") (pintype "tri_state"))
    )
    (net (code "61") (name "unconnected-(U5-Q6-Pad14)") (class "Default")
      (node (ref "U5") (pin "14") (pinfunction "Q6_14") (pintype "tri_state"))
    )
    (net (code "62") (name "unconnected-(U5-Q7-Pad13)") (class "Default")
      (node (ref "U5") (pin "13") (pinfunction "Q7_13") (pintype "tri_state"))
    )
    (net (code "63") (name "unconnected-(U5-Q8-Pad12)") (class "Default")
      (node (ref "U5") (pin "12") (pinfunction "Q8_12") (pintype "tri_state"))
    )
    (net (code "64") (name "unconnected-(USB1-D+-Pad3)") (class "Default")
      (node (ref "USB1") (pin "3") (pinfunction "D+_3") (pintype "passive"))
    )
    (net (code "65") (name "unconnected-(USB1-D+-Pad6)") (class "Default")
      (node (ref "USB1") (pin "6") (pinfunction "D+_6") (pintype "passive"))
    )
    (net (code "66") (name "unconnected-(USB1-D--Pad2)") (class "Default")
      (node (ref "USB1") (pin "2") (pinfunction "D-_2") (pintype "passive"))
    )
    (net (code "67") (name "unconnected-(USB1-D--Pad7)") (class "Default")
      (node (ref "USB1") (pin "7") (pinfunction "D-_7") (pintype "passive"))
    )
  )
)
